# STM32F030C8T6.net
KiCad netlist of a schematic drawn in Altium Designer
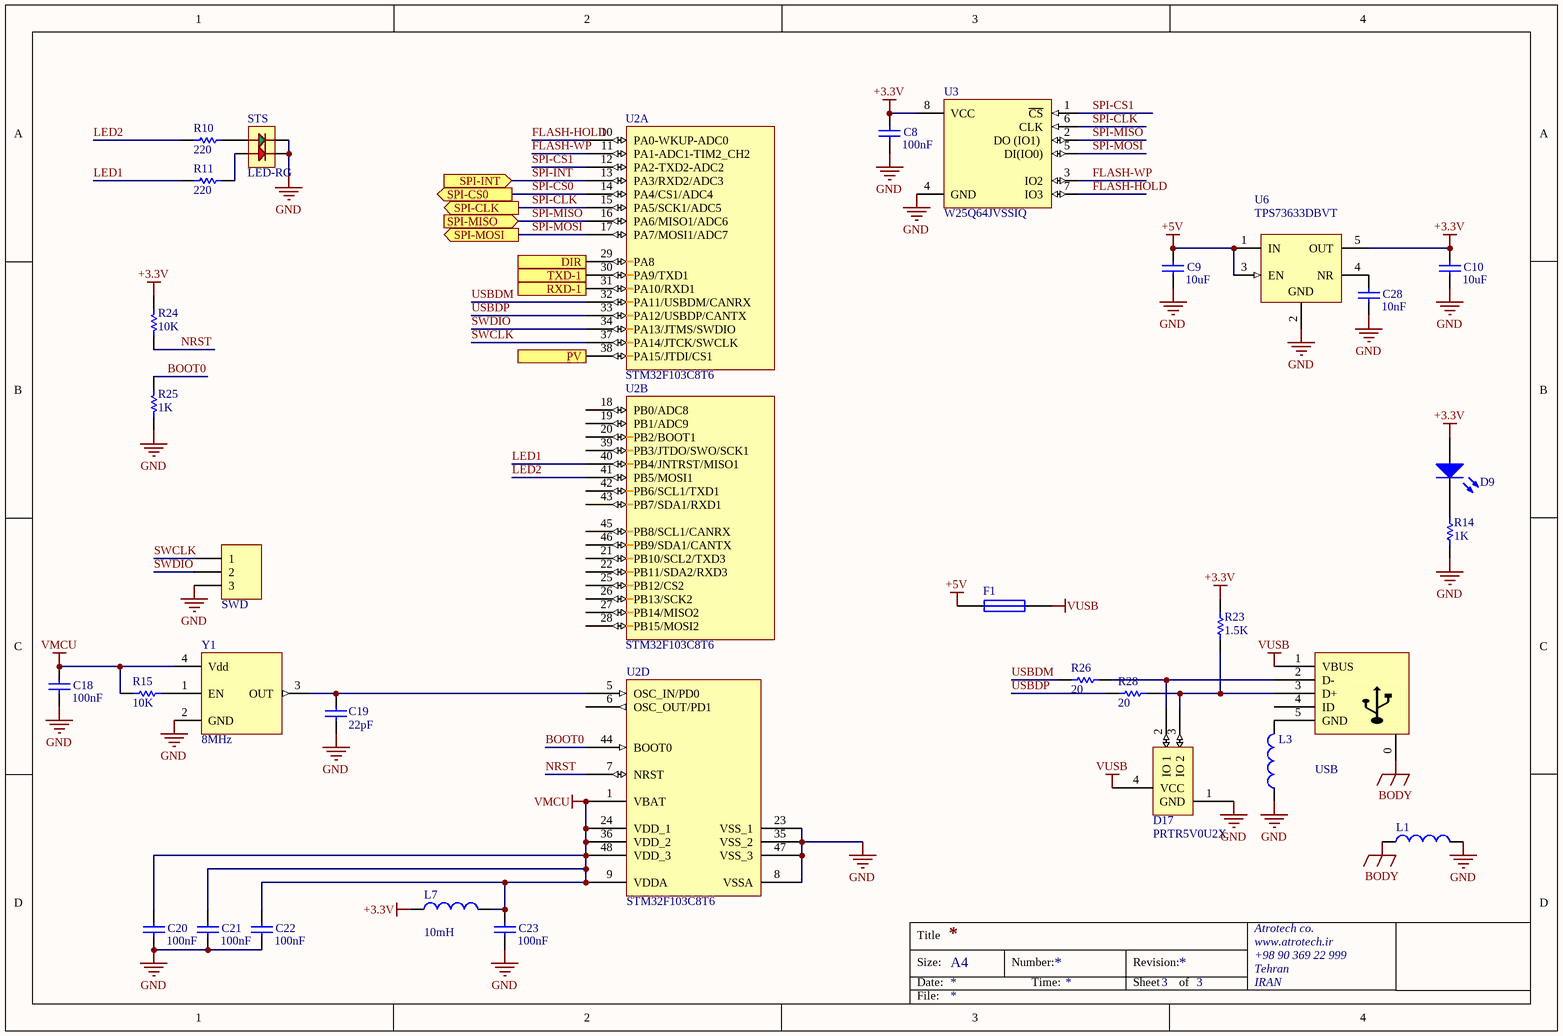
[diagram p0: STM32F030C8T6.SchDoc]

(export (version "E")
  (design (tool "Eeschema 10.0.6"))
  (components
    (comp (ref "C8")
      (value "100nF")
      (footprint "C603")
      (description "Capacitor")
      (fields (field (name "DESIGNER") "Parsa Malekpour"))
      (libsource (lib "UserPKG") (part "Cap"))
    )
    (comp (ref "C9")
      (value "10uF")
      (footprint "C805")
      (description "Capacitor")
      (fields (field (name "DESIGNER") "Parsa Malekpour"))
      (libsource (lib "UserPKG") (part "Cap"))
    )
    (comp (ref "C10")
      (value "10uF")
      (footprint "C805")
      (description "Capacitor")
      (fields (field (name "DESIGNER") "Parsa Malekpour"))
      (libsource (lib "UserPKG") (part "Cap"))
    )
    (comp (ref "C18")
      (value "100nF")
      (footprint "C603")
      (description "Capacitor")
      (fields (field (name "DESIGNER") "Parsa Malekpour"))
      (libsource (lib "UserPKG") (part "Cap"))
    )
    (comp (ref "C19")
      (value "22pF")
      (footprint "C603")
      (description "Capacitor")
      (fields (field (name "DESIGNER") "Parsa Malekpour"))
      (libsource (lib "UserPKG") (part "Cap"))
    )
    (comp (ref "C20")
      (value "100nF")
      (footprint "C603")
      (description "Capacitor")
      (fields (field (name "DESIGNER") "Parsa Malekpour"))
      (libsource (lib "UserPKG") (part "Cap"))
    )
    (comp (ref "C21")
      (value "100nF")
      (footprint "C603")
      (description "Capacitor")
      (fields (field (name "DESIGNER") "Parsa Malekpour"))
      (libsource (lib "UserPKG") (part "Cap"))
    )
    (comp (ref "C22")
      (value "100nF")
      (footprint "C603")
      (description "Capacitor")
      (fields (field (name "DESIGNER") "Parsa Malekpour"))
      (libsource (lib "UserPKG") (part "Cap"))
    )
    (comp (ref "C23")
      (value "100nF")
      (footprint "C603")
      (description "Capacitor")
      (fields (field (name "DESIGNER") "Parsa Malekpour"))
      (libsource (lib "UserPKG") (part "Cap"))
    )
    (comp (ref "C28")
      (value "10nF")
      (footprint "C603")
      (description "Capacitor")
      (fields (field (name "DESIGNER") "Parsa Malekpour"))
      (libsource (lib "UserPKG") (part "Cap"))
    )
    (comp (ref "D9") (value "LED") (footprint "led-0603") (libsource (lib "ParsaLibrary") (part "LED")))
    (comp (ref "D17")
      (value "PRTR5V0U2X")
      (footprint "SOT-143B")
      (description "Ultra low capacitance double rail-to-rail ESD protection diode")
      (libsource (lib "ParsaLibrary") (part "PRTR5V0U2X"))
    )
    (comp (ref "F1")
      (value "Fuse 1")
      (footprint "pARSALIBRARY:ptc-0805")
      (description "Fuse")
      (fields (field (name "PUBLISHER") "Altium Limited"))
      (libsource (lib "Miscellaneous Devices") (part "Fuse 1"))
    )
    (comp (ref "L1")
      (value "Inductor")
      (footprint "R805")
      (fields (field (name "PUBLISHER") "Altium Limited"))
      (libsource (lib "Miscellaneous Devices") (part "Inductor"))
    )
    (comp (ref "L3")
      (value "Inductor")
      (footprint "R805")
      (fields (field (name "PUBLISHER") "Altium Limited"))
      (libsource (lib "Miscellaneous Devices") (part "Inductor"))
    )
    (comp (ref "L7")
      (value "10mH")
      (footprint "R805")
      (description "Inductor")
      (fields (field (name "PUBLISHER") "Altium Limited"))
      (libsource (lib "Miscellaneous Devices") (part "Inductor"))
    )
    (comp (ref "R10")
      (value "220")
      (footprint "R0603")
      (description "Resistor")
      (fields (field (name "DESIGNER") "Parsa Malekpour"))
      (libsource (lib "ParsaLibrary") (part "Resistor"))
    )
    (comp (ref "R11")
      (value "220")
      (footprint "R0603")
      (description "Resistor")
      (fields (field (name "DESIGNER") "Parsa Malekpour"))
      (libsource (lib "ParsaLibrary") (part "Resistor"))
    )
    (comp (ref "R14")
      (value "1K")
      (footprint "R0603")
      (description "Resistor")
      (fields (field (name "DESIGNER") "Parsa Malekpour"))
      (libsource (lib "ParsaLibrary") (part "Resistor"))
    )
    (comp (ref "R15")
      (value "10K")
      (footprint "R0603")
      (description "Resistor")
      (fields (field (name "DESIGNER") "Parsa Malekpour"))
      (libsource (lib "ParsaLibrary") (part "Resistor"))
    )
    (comp (ref "R23")
      (value "1.5K")
      (footprint "R0603")
      (description "Resistor")
      (fields (field (name "DESIGNER") "Parsa Malekpour"))
      (libsource (lib "ParsaLibrary") (part "Resistor"))
    )
    (comp (ref "R24")
      (value "10K")
      (footprint "R0603")
      (description "Resistor")
      (fields (field (name "DESIGNER") "Parsa Malekpour"))
      (libsource (lib "UserPKG") (part "Resistor"))
    )
    (comp (ref "R25")
      (value "1K")
      (footprint "R0603")
      (description "Resistor")
      (fields (field (name "DESIGNER") "Parsa Malekpour"))
      (libsource (lib "UserPKG") (part "Resistor"))
    )
    (comp (ref "R26")
      (value "20")
      (footprint "R0603")
      (description "Resistor")
      (fields (field (name "DESIGNER") "Parsa Malekpour"))
      (libsource (lib "ParsaLibrary") (part "Resistor"))
    )
    (comp (ref "R28")
      (value "20")
      (footprint "R0603")
      (description "Resistor")
      (fields (field (name "DESIGNER") "Parsa Malekpour"))
      (libsource (lib "ParsaLibrary") (part "Resistor"))
    )
    (comp (ref "STS")
      (value "LED-RG")
      (footprint "LED-1210")
      (libsource (lib "ParsaLibrary") (part "LED-RG-4"))
    )
    (comp (ref "SWD")
      (value "CONN-3")
      (footprint "PHDR3")
      (description "Header, 3-Pin")
      (libsource (lib "ParsaLibrary") (part "CONN-3"))
    )
    (comp (ref "U2")
      (value "STM32F103C8T6")
      (footprint "LQFP-48")
      (description "STM32 ARM-based 32-bit MCU with 64 Kbytes Flash, 48-pin LQFP, Industrial Temperature")
      (fields (field (name "PUBLISHER") "Altium Limited"))
      (libsource (lib "ParsaLibrary") (part "STM32F103C8T6"))
    )
    (comp (ref "U3")
      (value "W25Q64JVSSIQ")
      (footprint "SOIC-8W")
      (libsource (lib "ParsaLibrary") (part "W25Q64JVSSIQ"))
    )
    (comp (ref "U6")
      (value "TPS73633DBVT")
      (footprint "DBV0005A_M")
      (fields (field (name "MANUFACTURER") "Texas Instruments"))
      (libsource (lib "Altium Content Vault") (part "TI-TPS79NXX-YYSOT5"))
    )
    (comp (ref "USB")
      (value "USB MINI")
      (footprint "USB-MINI-SMD")
      (libsource (lib "ParsaLibrary") (part "USB MINI"))
    )
    (comp (ref "Y1")
      (value "8MHz")
      (footprint "ASV")
      (description "OSCILLATOR")
      (fields (field (name "FREQUENCY") "8MHz"))
      (libsource (lib "ParsaLibrary") (part "OSCILLATOR"))
    )
  )
  (nets
    (net (code "1") (name "+3.3V") (class "Default")
      (node (ref "C10") (pin "2") (pinfunction "2_2") (pintype "passive"))
      (node (ref "C8") (pin "2") (pinfunction "2_2") (pintype "passive"))
      (node (ref "D9") (pin "1") (pinfunction "A_1") (pintype "passive"))
      (node (ref "L7") (pin "1") (pinfunction "1_1") (pintype "passive"))
      (node (ref "R23") (pin "1") (pinfunction "1_1") (pintype "passive"))
      (node (ref "R24") (pin "2") (pinfunction "2_2") (pintype "passive"))
      (node (ref "U3") (pin "8") (pinfunction "VCC_8") (pintype "power_in"))
      (node (ref "U6") (pin "5") (pinfunction "OUT_5") (pintype "power_in"))
    )
    (net (code "2") (name "+5V") (class "Default")
      (node (ref "C9") (pin "2") (pinfunction "2_2") (pintype "passive"))
      (node (ref "F1") (pin "1") (pinfunction "1_1") (pintype "passive"))
      (node (ref "U6") (pin "1") (pinfunction "IN_1") (pintype "power_in"))
      (node (ref "U6") (pin "3") (pinfunction "EN_3") (pintype "input"))
    )
    (net (code "3") (name "/BOOT0") (class "Default")
      (node (ref "R25") (pin "2") (pinfunction "2_2") (pintype "passive"))
      (node (ref "U2") (pin "44") (pinfunction "BOOT0_44") (pintype "input"))
    )
    (net (code "4") (name "/DIR") (class "Default")
      (node (ref "U2") (pin "29") (pinfunction "PA8_29") (pintype "bidirectional"))
    )
    (net (code "5") (name "/FLASH-HOLD") (class "Default")
      (node (ref "U2") (pin "10") (pinfunction "PA0-WKUP-ADC0_10") (pintype "bidirectional"))
      (node (ref "U3") (pin "7") (pinfunction "IO3_7") (pintype "bidirectional"))
    )
    (net (code "6") (name "/FLASH-WP") (class "Default")
      (node (ref "U2") (pin "11") (pinfunction "PA1-ADC1-TIM2_CH2_11") (pintype "bidirectional"))
      (node (ref "U3") (pin "3") (pinfunction "IO2_3") (pintype "bidirectional"))
    )
    (net (code "7") (name "/LED1") (class "Default")
      (node (ref "R11") (pin "2") (pinfunction "2_2") (pintype "passive"))
      (node (ref "U2") (pin "40") (pinfunction "PB4/JNTRST/MISO1_40") (pintype "bidirectional"))
    )
    (net (code "8") (name "/LED2") (class "Default")
      (node (ref "R10") (pin "2") (pinfunction "2_2") (pintype "passive"))
      (node (ref "U2") (pin "41") (pinfunction "PB5/MOSI1_41") (pintype "bidirectional"))
    )
    (net (code "9") (name "/NRST") (class "Default")
      (node (ref "R24") (pin "1") (pinfunction "1_1") (pintype "passive"))
      (node (ref "U2") (pin "7") (pinfunction "NRST_7") (pintype "bidirectional"))
    )
    (net (code "10") (name "/PV") (class "Default")
      (node (ref "U2") (pin "38") (pinfunction "PA15/JTDI/CS1_38") (pintype "bidirectional"))
    )
    (net (code "11") (name "/RXD-1") (class "Default")
      (node (ref "U2") (pin "31") (pinfunction "PA10/RXD1_31") (pintype "bidirectional"))
    )
    (net (code "12") (name "/SPI-CLK") (class "Default")
      (node (ref "U2") (pin "15") (pinfunction "PA5/SCK1/ADC5_15") (pintype "bidirectional"))
      (node (ref "U3") (pin "6") (pinfunction "CLK_6") (pintype "input"))
    )
    (net (code "13") (name "/SPI-CS0") (class "Default")
      (node (ref "U2") (pin "14") (pinfunction "PA4/CS1/ADC4_14") (pintype "bidirectional"))
    )
    (net (code "14") (name "/SPI-CS1") (class "Default")
      (node (ref "U2") (pin "12") (pinfunction "PA2-TXD2-ADC2_12") (pintype "bidirectional"))
      (node (ref "U3") (pin "1") (pinfunction "~{CS}_1") (pintype "input"))
    )
    (net (code "15") (name "/SPI-INT") (class "Default")
      (node (ref "U2") (pin "13") (pinfunction "PA3/RXD2/ADC3_13") (pintype "bidirectional"))
    )
    (net (code "16") (name "/SPI-MISO") (class "Default")
      (node (ref "U2") (pin "16") (pinfunction "PA6/MISO1/ADC6_16") (pintype "bidirectional"))
      (node (ref "U3") (pin "2") (pinfunction "DO_(IO1)_2") (pintype "bidirectional"))
    )
    (net (code "17") (name "/SPI-MOSI") (class "Default")
      (node (ref "U2") (pin "17") (pinfunction "PA7/MOSI1/ADC7_17") (pintype "bidirectional"))
      (node (ref "U3") (pin "5") (pinfunction "DI(IO0)_5") (pintype "bidirectional"))
    )
    (net (code "18") (name "/SWCLK") (class "Default")
      (node (ref "SWD") (pin "1") (pinfunction "1_1") (pintype "passive"))
      (node (ref "U2") (pin "37") (pinfunction "PA14/JTCK/SWCLK_37") (pintype "bidirectional"))
    )
    (net (code "19") (name "/SWDIO") (class "Default")
      (node (ref "SWD") (pin "2") (pinfunction "2_2") (pintype "passive"))
      (node (ref "U2") (pin "34") (pinfunction "PA13/JTMS/SWDIO_34") (pintype "bidirectional"))
    )
    (net (code "20") (name "/TXD-1") (class "Default")
      (node (ref "U2") (pin "30") (pinfunction "PA9/TXD1_30") (pintype "bidirectional"))
    )
    (net (code "21") (name "/USBDM") (class "Default")
      (node (ref "R26") (pin "2") (pinfunction "2_2") (pintype "passive"))
      (node (ref "U2") (pin "32") (pinfunction "PA11/USBDM/CANRX_32") (pintype "bidirectional"))
    )
    (net (code "22") (name "/USBDP") (class "Default")
      (node (ref "R28") (pin "2") (pinfunction "2_2") (pintype "passive"))
      (node (ref "U2") (pin "33") (pinfunction "PA12/USBDP/CANTX_33") (pintype "bidirectional"))
    )
    (net (code "23") (name "BODY") (class "Default")
      (node (ref "L1") (pin "1") (pinfunction "1_1") (pintype "passive"))
      (node (ref "USB") (pin "0") (pinfunction "BODY_0") (pintype "passive"))
    )
    (net (code "24") (name "GND") (class "Default")
      (node (ref "C10") (pin "1") (pinfunction "1_1") (pintype "passive"))
      (node (ref "C18") (pin "1") (pinfunction "1_1") (pintype "passive"))
      (node (ref "C19") (pin "2") (pinfunction "2_2") (pintype "passive"))
      (node (ref "C20") (pin "1") (pinfunction "1_1") (pintype "passive"))
      (node (ref "C21") (pin "1") (pinfunction "1_1") (pintype "passive"))
      (node (ref "C22") (pin "1") (pinfunction "1_1") (pintype "passive"))
      (node (ref "C23") (pin "1") (pinfunction "1_1") (pintype "passive"))
      (node (ref "C28") (pin "1") (pinfunction "1_1") (pintype "passive"))
      (node (ref "C8") (pin "1") (pinfunction "1_1") (pintype "passive"))
      (node (ref "C9") (pin "1") (pinfunction "1_1") (pintype "passive"))
      (node (ref "D17") (pin "1") (pinfunction "GND_1") (pintype "power_in"))
      (node (ref "L1") (pin "2") (pinfunction "2_2") (pintype "passive"))
      (node (ref "L3") (pin "1") (pinfunction "1_1") (pintype "passive"))
      (node (ref "R14") (pin "2") (pinfunction "2_2") (pintype "passive"))
      (node (ref "R25") (pin "1") (pinfunction "1_1") (pintype "passive"))
      (node (ref "STS") (pin "3") (pinfunction "RED-C_3") (pintype "passive"))
      (node (ref "STS") (pin "4") (pinfunction "GRN-C_4") (pintype "passive"))
      (node (ref "SWD") (pin "3") (pinfunction "3_3") (pintype "passive"))
      (node (ref "U2") (pin "23") (pinfunction "VSS_1_23") (pintype "power_in"))
      (node (ref "U2") (pin "35") (pinfunction "VSS_2_35") (pintype "power_in"))
      (node (ref "U2") (pin "47") (pinfunction "VSS_3_47") (pintype "power_in"))
      (node (ref "U2") (pin "8") (pinfunction "VSSA_8") (pintype "power_in"))
      (node (ref "U3") (pin "4") (pinfunction "GND_4") (pintype "power_in"))
      (node (ref "U6") (pin "2") (pinfunction "GND_2") (pintype "power_in"))
      (node (ref "Y1") (pin "2") (pinfunction "GND_2") (pintype "passive"))
    )
    (net (code "25") (name "Net-(D9-K)") (class "Default")
      (node (ref "D9") (pin "2") (pinfunction "K_2") (pintype "passive"))
      (node (ref "R14") (pin "1") (pinfunction "1_1") (pintype "passive"))
    )
    (net (code "26") (name "Net-(D17-IO_1)") (class "Default")
      (node (ref "D17") (pin "2") (pinfunction "IO_1_2") (pintype "bidirectional"))
      (node (ref "R26") (pin "1") (pinfunction "1_1") (pintype "passive"))
      (node (ref "USB") (pin "2") (pinfunction "D-_2") (pintype "passive"))
    )
    (net (code "27") (name "Net-(D17-IO_2)") (class "Default")
      (node (ref "D17") (pin "3") (pinfunction "IO_2_3") (pintype "bidirectional"))
      (node (ref "R23") (pin "2") (pinfunction "2_2") (pintype "passive"))
      (node (ref "R28") (pin "1") (pinfunction "1_1") (pintype "passive"))
      (node (ref "USB") (pin "3") (pinfunction "D+_3") (pintype "passive"))
    )
    (net (code "28") (name "Net-(STS-GRN-A)") (class "Default")
      (node (ref "R10") (pin "1") (pinfunction "1_1") (pintype "passive"))
      (node (ref "STS") (pin "1") (pinfunction "GRN-A_1") (pintype "passive"))
    )
    (net (code "29") (name "Net-(STS-RED-A)") (class "Default")
      (node (ref "R11") (pin "1") (pinfunction "1_1") (pintype "passive"))
      (node (ref "STS") (pin "2") (pinfunction "RED-A_2") (pintype "passive"))
    )
    (net (code "30") (name "Net-(U2D-OSC_IN{slash}PD0)") (class "Default")
      (node (ref "C19") (pin "1") (pinfunction "1_1") (pintype "passive"))
      (node (ref "U2") (pin "5") (pinfunction "OSC_IN/PD0_5") (pintype "input"))
      (node (ref "Y1") (pin "3") (pinfunction "OUT_3") (pintype "output"))
    )
    (net (code "31") (name "Net-(U6-NR)") (class "Default")
      (node (ref "C28") (pin "2") (pinfunction "2_2") (pintype "passive"))
      (node (ref "U6") (pin "4") (pinfunction "NR_4") (pintype "passive"))
    )
    (net (code "32") (name "Net-(USB-GND)") (class "Default")
      (node (ref "L3") (pin "2") (pinfunction "2_2") (pintype "passive"))
      (node (ref "USB") (pin "5") (pinfunction "GND_5") (pintype "power_in"))
    )
    (net (code "33") (name "Net-(Y1-EN)") (class "Default")
      (node (ref "R15") (pin "1") (pinfunction "1_1") (pintype "passive"))
      (node (ref "Y1") (pin "1") (pinfunction "EN_1") (pintype "passive"))
    )
    (net (code "34") (name "VMCU") (class "Default")
      (node (ref "C18") (pin "2") (pinfunction "2_2") (pintype "passive"))
      (node (ref "C20") (pin "2") (pinfunction "2_2") (pintype "passive"))
      (node (ref "C21") (pin "2") (pinfunction "2_2") (pintype "passive"))
      (node (ref "C22") (pin "2") (pinfunction "2_2") (pintype "passive"))
      (node (ref "C23") (pin "2") (pinfunction "2_2") (pintype "passive"))
      (node (ref "L7") (pin "2") (pinfunction "2_2") (pintype "passive"))
      (node (ref "R15") (pin "2") (pinfunction "2_2") (pintype "passive"))
      (node (ref "U2") (pin "1") (pinfunction "VBAT_1") (pintype "power_in"))
      (node (ref "U2") (pin "24") (pinfunction "VDD_1_24") (pintype "power_in"))
      (node (ref "U2") (pin "36") (pinfunction "VDD_2_36") (pintype "power_in"))
      (node (ref "U2") (pin "48") (pinfunction "VDD_3_48") (pintype "power_in"))
      (node (ref "U2") (pin "9") (pinfunction "VDDA_9") (pintype "power_in"))
      (node (ref "Y1") (pin "4") (pinfunction "Vdd_4") (pintype "passive"))
    )
    (net (code "35") (name "VUSB") (class "Default")
      (node (ref "D17") (pin "4") (pinfunction "VCC_4") (pintype "power_in"))
      (node (ref "F1") (pin "2") (pinfunction "2_2") (pintype "passive"))
      (node (ref "USB") (pin "1") (pinfunction "VBUS_1") (pintype "power_in"))
    )
    (net (code "36") (name "unconnected-(U2B-PB0{slash}ADC8-Pad18)") (class "Default")
      (node (ref "U2") (pin "18") (pinfunction "PB0/ADC8_18") (pintype "bidirectional"))
    )
    (net (code "37") (name "unconnected-(U2B-PB1{slash}ADC9-Pad19)") (class "Default")
      (node (ref "U2") (pin "19") (pinfunction "PB1/ADC9_19") (pintype "bidirectional"))
    )
    (net (code "38") (name "unconnected-(U2B-PB2{slash}BOOT1-Pad20)") (class "Default")
      (node (ref "U2") (pin "20") (pinfunction "PB2/BOOT1_20") (pintype "bidirectional"))
    )
    (net (code "39") (name "unconnected-(U2B-PB3{slash}JTDO{slash}SWO{slash}SCK1-Pad39)") (class "Default")
      (node (ref "U2") (pin "39") (pinfunction "PB3/JTDO/SWO/SCK1_39") (pintype "bidirectional"))
    )
    (net (code "40") (name "unconnected-(U2B-PB6{slash}SCL1{slash}TXD1-Pad42)") (class "Default")
      (node (ref "U2") (pin "42") (pinfunction "PB6/SCL1/TXD1_42") (pintype "bidirectional"))
    )
    (net (code "41") (name "unconnected-(U2B-PB7{slash}SDA1{slash}RXD1-Pad43)") (class "Default")
      (node (ref "U2") (pin "43") (pinfunction "PB7/SDA1/RXD1_43") (pintype "bidirectional"))
    )
    (net (code "42") (name "unconnected-(U2B-PB8{slash}SCL1{slash}CANRX-Pad45)") (class "Default")
      (node (ref "U2") (pin "45") (pinfunction "PB8/SCL1/CANRX_45") (pintype "bidirectional"))
    )
    (net (code "43") (name "unconnected-(U2B-PB9{slash}SDA1{slash}CANTX-Pad46)") (class "Default")
      (node (ref "U2") (pin "46") (pinfunction "PB9/SDA1/CANTX_46") (pintype "bidirectional"))
    )
    (net (code "44") (name "unconnected-(U2B-PB10{slash}SCL2{slash}TXD3-Pad21)") (class "Default")
      (node (ref "U2") (pin "21") (pinfunction "PB10/SCL2/TXD3_21") (pintype "bidirectional"))
    )
    (net (code "45") (name "unconnected-(U2B-PB11{slash}SDA2{slash}RXD3-Pad22)") (class "Default")
      (node (ref "U2") (pin "22") (pinfunction "PB11/SDA2/RXD3_22") (pintype "bidirectional"))
    )
    (net (code "46") (name "unconnected-(U2B-PB12{slash}CS2-Pad25)") (class "Default")
      (node (ref "U2") (pin "25") (pinfunction "PB12/CS2_25") (pintype "bidirectional"))
    )
    (net (code "47") (name "unconnected-(U2B-PB13{slash}SCK2-Pad26)") (class "Default")
      (node (ref "U2") (pin "26") (pinfunction "PB13/SCK2_26") (pintype "bidirectional"))
    )
    (net (code "48") (name "unconnected-(U2B-PB14{slash}MISO2-Pad27)") (class "Default")
      (node (ref "U2") (pin "27") (pinfunction "PB14/MISO2_27") (pintype "bidirectional"))
    )
    (net (code "49") (name "unconnected-(U2B-PB15{slash}MOSI2-Pad28)") (class "Default")
      (node (ref "U2") (pin "28") (pinfunction "PB15/MOSI2_28") (pintype "bidirectional"))
    )
    (net (code "50") (name "unconnected-(U2D-OSC_OUT{slash}PD1-Pad6)") (class "Default")
      (node (ref "U2") (pin "6") (pinfunction "OSC_OUT/PD1_6") (pintype "output"))
    )
    (net (code "51") (name "unconnected-(USB-ID-Pad4)") (class "Default")
      (node (ref "USB") (pin "4") (pinfunction "ID_4") (pintype "power_in"))
    )
  )
)
